# AutoISP328.net
KiCad netlist of a schematic drawn in EAGLE
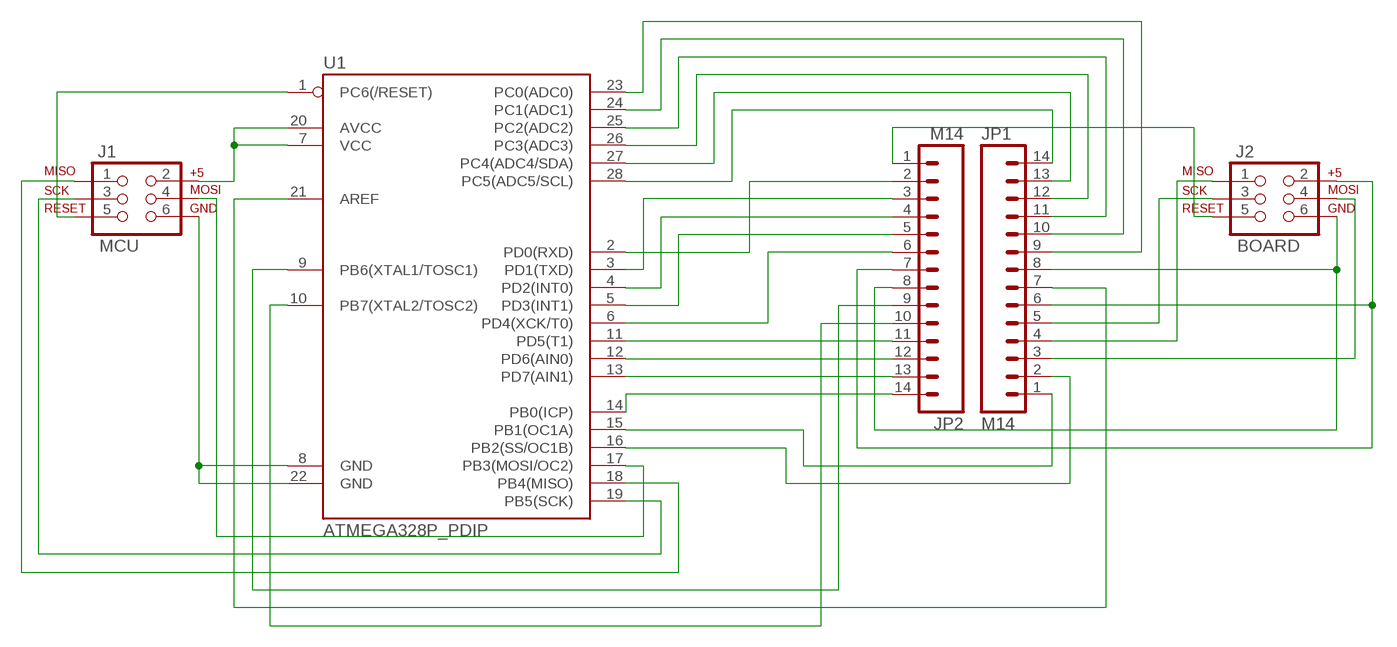
[diagram p0: schematic, sheet 1]

(export (version "E")
  (design (tool "Eeschema 10.0.6"))
  (components
    (comp (ref "J1")
      (value "MCU")
      (footprint "eagle-import:2X3")
      (libsource (lib "eagle-import") (part "AVR_SPI_PRG_6PTH"))
    )
    (comp (ref "J2")
      (value "BOARD")
      (footprint "eagle-import:2X3")
      (libsource (lib "eagle-import") (part "AVR_SPI_PRG_6PTH"))
    )
    (comp (ref "JP1")
      (value "M14")
      (footprint "eagle-import:1X14")
      (libsource (lib "eagle-import") (part "M14"))
    )
    (comp (ref "JP2")
      (value "M14")
      (footprint "eagle-import:1X14")
      (libsource (lib "eagle-import") (part "M14"))
    )
    (comp (ref "U1")
      (value "ATMEGA328P_PDIP")
      (footprint "eagle-import:DIL28-3")
      (libsource (lib "eagle-import") (part "ATMEGA328P_PDIP"))
    )
  )
  (nets
    (net (code "1") (name "Net-(J1-Pad6)") (class "Default")
      (node (ref "J1") (pin "6") (pinfunction "6_6") (pintype "passive"))
      (node (ref "U1") (pin "22") (pinfunction "GND_22") (pintype "bidirectional"))
      (node (ref "U1") (pin "8") (pinfunction "GND_8") (pintype "bidirectional"))
    )
    (net (code "2") (name "Net-(J2-Pad1)") (class "Default")
      (node (ref "J2") (pin "1") (pinfunction "1_1") (pintype "passive"))
      (node (ref "JP1") (pin "4") (pinfunction "4_4") (pintype "passive"))
    )
    (net (code "3") (name "Net-(J2-Pad2)") (class "Default")
      (node (ref "J2") (pin "2") (pinfunction "2_2") (pintype "passive"))
      (node (ref "JP1") (pin "6") (pinfunction "6_6") (pintype "passive"))
      (node (ref "JP2") (pin "7") (pinfunction "7_7") (pintype "passive"))
    )
    (net (code "4") (name "Net-(J2-Pad3)") (class "Default")
      (node (ref "J2") (pin "3") (pinfunction "3_3") (pintype "passive"))
      (node (ref "JP1") (pin "5") (pinfunction "5_5") (pintype "passive"))
    )
    (net (code "5") (name "Net-(J2-Pad4)") (class "Default")
      (node (ref "J2") (pin "4") (pinfunction "4_4") (pintype "passive"))
      (node (ref "JP1") (pin "3") (pinfunction "3_3") (pintype "passive"))
    )
    (net (code "6") (name "Net-(J2-Pad5)") (class "Default")
      (node (ref "J2") (pin "5") (pinfunction "5_5") (pintype "passive"))
      (node (ref "JP2") (pin "1") (pinfunction "1_1") (pintype "passive"))
    )
    (net (code "7") (name "Net-(J2-Pad6)") (class "Default")
      (node (ref "J2") (pin "6") (pinfunction "6_6") (pintype "passive"))
      (node (ref "JP1") (pin "8") (pinfunction "8_8") (pintype "passive"))
      (node (ref "JP2") (pin "8") (pinfunction "8_8") (pintype "passive"))
    )
    (net (code "8") (name "Net-(U1-AREF)") (class "Default")
      (node (ref "JP1") (pin "7") (pinfunction "7_7") (pintype "passive"))
      (node (ref "U1") (pin "21") (pinfunction "AREF_21") (pintype "bidirectional"))
    )
    (net (code "9") (name "Net-(U1-AVCC)") (class "Default")
      (node (ref "J1") (pin "2") (pinfunction "2_2") (pintype "passive"))
      (node (ref "U1") (pin "20") (pinfunction "AVCC_20") (pintype "bidirectional"))
      (node (ref "U1") (pin "7") (pinfunction "VCC_7") (pintype "bidirectional"))
    )
    (net (code "10") (name "Net-(U1-PB0(ICP))") (class "Default")
      (node (ref "JP2") (pin "14") (pinfunction "14_14") (pintype "passive"))
      (node (ref "U1") (pin "14") (pinfunction "PB0(ICP)_14") (pintype "bidirectional"))
    )
    (net (code "11") (name "Net-(U1-PB1(OC1A))") (class "Default")
      (node (ref "JP1") (pin "1") (pinfunction "1_1") (pintype "passive"))
      (node (ref "U1") (pin "15") (pinfunction "PB1(OC1A)_15") (pintype "bidirectional"))
    )
    (net (code "12") (name "Net-(U1-PB2(SS{slash}OC1B))") (class "Default")
      (node (ref "JP1") (pin "2") (pinfunction "2_2") (pintype "passive"))
      (node (ref "U1") (pin "16") (pinfunction "PB2(SS/OC1B)_16") (pintype "bidirectional"))
    )
    (net (code "13") (name "Net-(U1-PB3(MOSI{slash}OC2))") (class "Default")
      (node (ref "J1") (pin "4") (pinfunction "4_4") (pintype "passive"))
      (node (ref "U1") (pin "17") (pinfunction "PB3(MOSI/OC2)_17") (pintype "bidirectional"))
    )
    (net (code "14") (name "Net-(U1-PB4(MISO))") (class "Default")
      (node (ref "J1") (pin "1") (pinfunction "1_1") (pintype "passive"))
      (node (ref "U1") (pin "18") (pinfunction "PB4(MISO)_18") (pintype "bidirectional"))
    )
    (net (code "15") (name "Net-(U1-PB5(SCK))") (class "Default")
      (node (ref "J1") (pin "3") (pinfunction "3_3") (pintype "passive"))
      (node (ref "U1") (pin "19") (pinfunction "PB5(SCK)_19") (pintype "bidirectional"))
    )
    (net (code "16") (name "Net-(U1-PB6(XTAL1{slash}TOSC1))") (class "Default")
      (node (ref "JP2") (pin "9") (pinfunction "9_9") (pintype "passive"))
      (node (ref "U1") (pin "9") (pinfunction "PB6(XTAL1/TOSC1)_9") (pintype "bidirectional"))
    )
    (net (code "17") (name "Net-(U1-PB7(XTAL2{slash}TOSC2))") (class "Default")
      (node (ref "JP2") (pin "10") (pinfunction "10_10") (pintype "passive"))
      (node (ref "U1") (pin "10") (pinfunction "PB7(XTAL2/TOSC2)_10") (pintype "bidirectional"))
    )
    (net (code "18") (name "Net-(U1-PC0(ADC0))") (class "Default")
      (node (ref "JP1") (pin "9") (pinfunction "9_9") (pintype "passive"))
      (node (ref "U1") (pin "23") (pinfunction "PC0(ADC0)_23") (pintype "bidirectional"))
    )
    (net (code "19") (name "Net-(U1-PC1(ADC1))") (class "Default")
      (node (ref "JP1") (pin "10") (pinfunction "10_10") (pintype "passive"))
      (node (ref "U1") (pin "24") (pinfunction "PC1(ADC1)_24") (pintype "bidirectional"))
    )
    (net (code "20") (name "Net-(U1-PC2(ADC2))") (class "Default")
      (node (ref "JP1") (pin "11") (pinfunction "11_11") (pintype "passive"))
      (node (ref "U1") (pin "25") (pinfunction "PC2(ADC2)_25") (pintype "bidirectional"))
    )
    (net (code "21") (name "Net-(U1-PC3(ADC3))") (class "Default")
      (node (ref "JP1") (pin "12") (pinfunction "12_12") (pintype "passive"))
      (node (ref "U1") (pin "26") (pinfunction "PC3(ADC3)_26") (pintype "bidirectional"))
    )
    (net (code "22") (name "Net-(U1-PC4(ADC4{slash}SDA))") (class "Default")
      (node (ref "JP1") (pin "13") (pinfunction "13_13") (pintype "passive"))
      (node (ref "U1") (pin "27") (pinfunction "PC4(ADC4/SDA)_27") (pintype "bidirectional"))
    )
    (net (code "23") (name "Net-(U1-PC5(ADC5{slash}SCL))") (class "Default")
      (node (ref "JP1") (pin "14") (pinfunction "14_14") (pintype "passive"))
      (node (ref "U1") (pin "28") (pinfunction "PC5(ADC5/SCL)_28") (pintype "bidirectional"))
    )
    (net (code "24") (name "Net-(U1-PC6({slash}RESET))") (class "Default")
      (node (ref "J1") (pin "5") (pinfunction "5_5") (pintype "passive"))
      (node (ref "U1") (pin "1") (pinfunction "PC6(/RESET)_1") (pintype "bidirectional"))
    )
    (net (code "25") (name "Net-(U1-PD0(RXD))") (class "Default")
      (node (ref "JP2") (pin "2") (pinfunction "2_2") (pintype "passive"))
      (node (ref "U1") (pin "2") (pinfunction "PD0(RXD)_2") (pintype "bidirectional"))
    )
    (net (code "26") (name "Net-(U1-PD1(TXD))") (class "Default")
      (node (ref "JP2") (pin "3") (pinfunction "3_3") (pintype "passive"))
      (node (ref "U1") (pin "3") (pinfunction "PD1(TXD)_3") (pintype "bidirectional"))
    )
    (net (code "27") (name "Net-(U1-PD2(INT0))") (class "Default")
      (node (ref "JP2") (pin "4") (pinfunction "4_4") (pintype "passive"))
      (node (ref "U1") (pin "4") (pinfunction "PD2(INT0)_4") (pintype "bidirectional"))
    )
    (net (code "28") (name "Net-(U1-PD3(INT1))") (class "Default")
      (node (ref "JP2") (pin "5") (pinfunction "5_5") (pintype "passive"))
      (node (ref "U1") (pin "5") (pinfunction "PD3(INT1)_5") (pintype "bidirectional"))
    )
    (net (code "29") (name "Net-(U1-PD4(XCK{slash}T0))") (class "Default")
      (node (ref "JP2") (pin "6") (pinfunction "6_6") (pintype "passive"))
      (node (ref "U1") (pin "6") (pinfunction "PD4(XCK/T0)_6") (pintype "bidirectional"))
    )
    (net (code "30") (name "Net-(U1-PD5(T1))") (class "Default")
      (node (ref "JP2") (pin "11") (pinfunction "11_11") (pintype "passive"))
      (node (ref "U1") (pin "11") (pinfunction "PD5(T1)_11") (pintype "bidirectional"))
    )
    (net (code "31") (name "Net-(U1-PD6(AIN0))") (class "Default")
      (node (ref "JP2") (pin "12") (pinfunction "12_12") (pintype "passive"))
      (node (ref "U1") (pin "12") (pinfunction "PD6(AIN0)_12") (pintype "bidirectional"))
    )
    (net (code "32") (name "Net-(U1-PD7(AIN1))") (class "Default")
      (node (ref "JP2") (pin "13") (pinfunction "13_13") (pintype "passive"))
      (node (ref "U1") (pin "13") (pinfunction "PD7(AIN1)_13") (pintype "bidirectional"))
    )
  )
)
